# BeeBlue.net
KiCad netlist of a schematic drawn in EAGLE
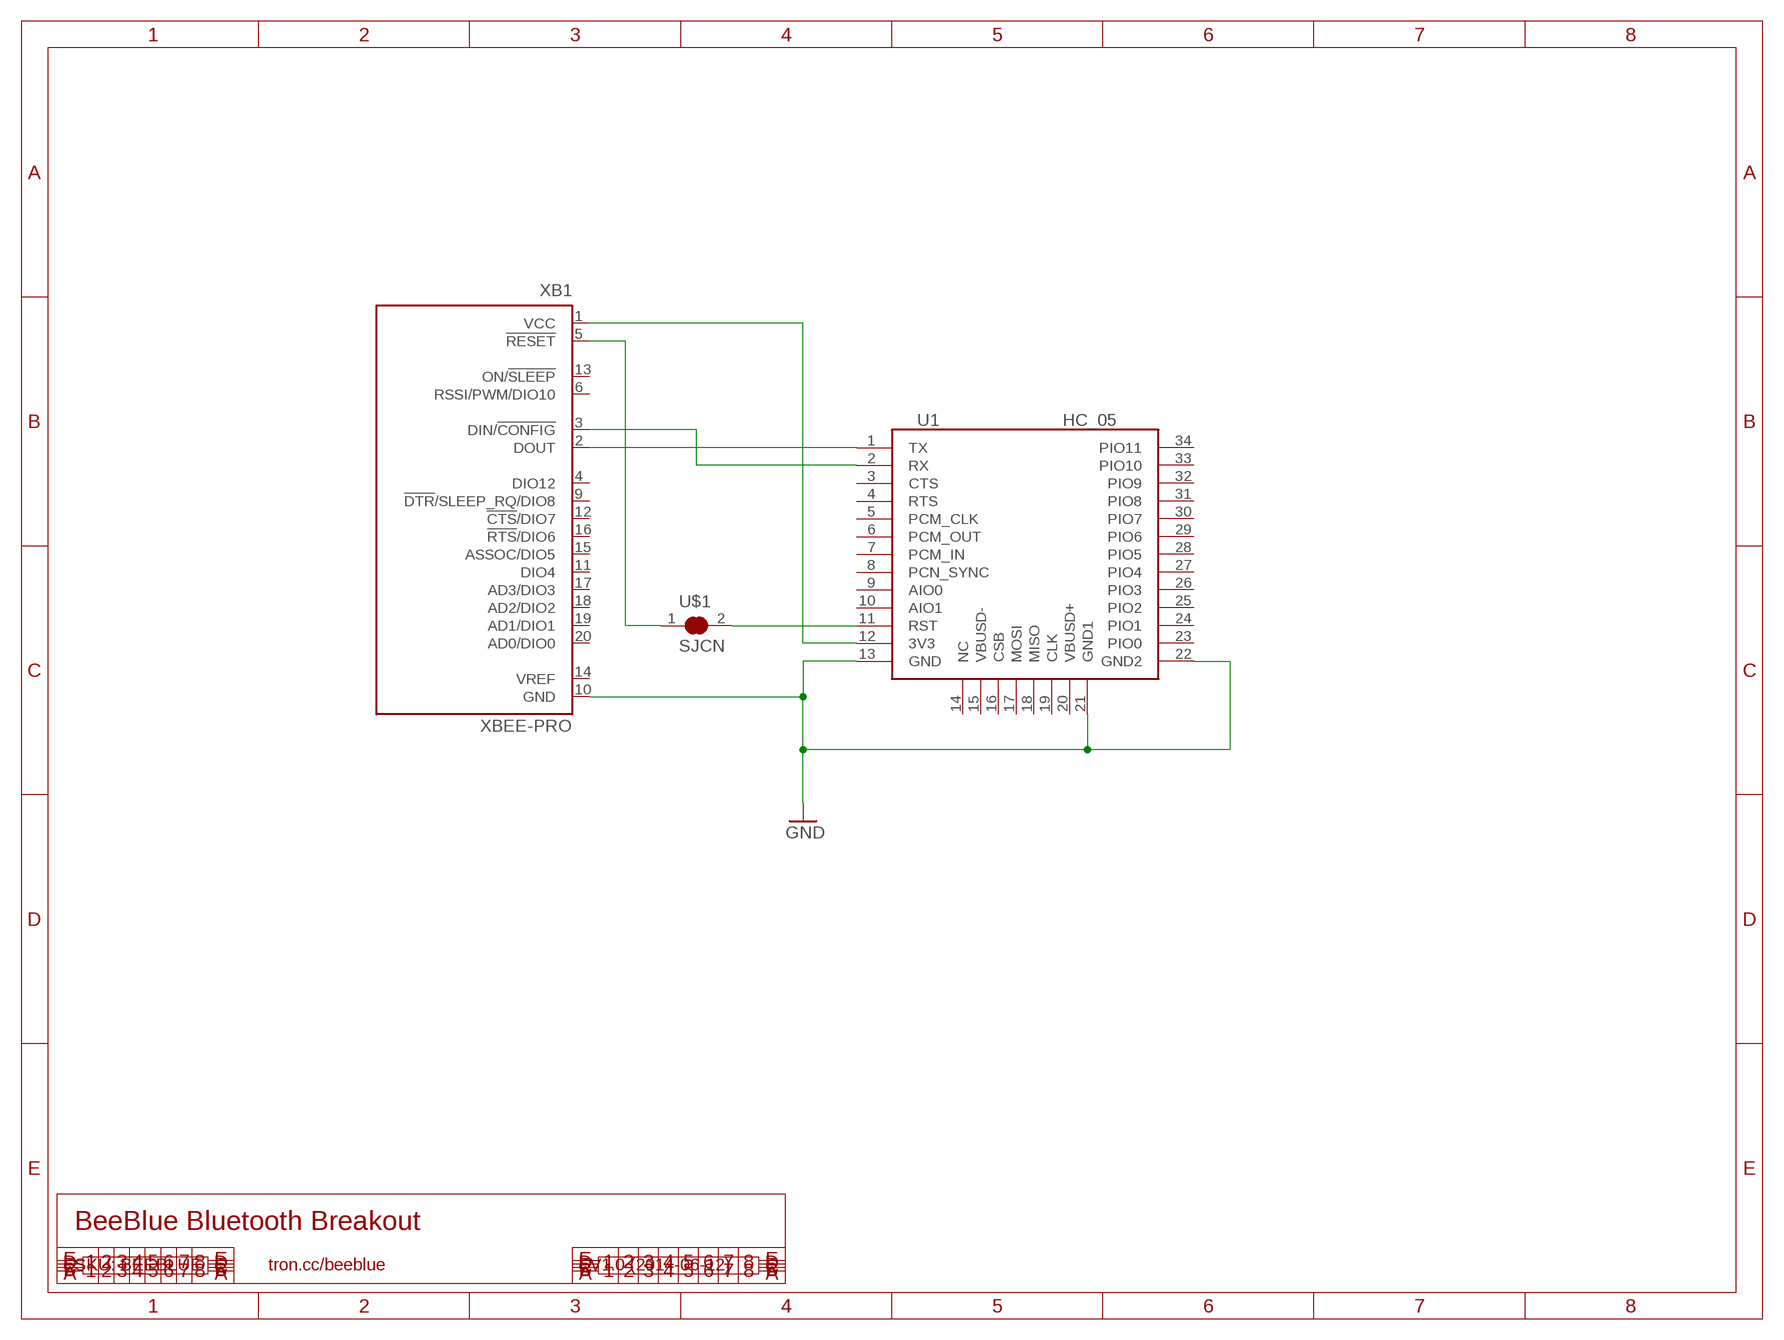
[diagram p0: schematic, sheet 1]

(export (version "E")
  (design (tool "Eeschema 10.0.6"))
  (components
    (comp (ref "U$1")
      (value "SJCN")
      (footprint "eagle-import:SJC")
      (libsource (lib "eagle-import") (part "SJCN"))
    )
    (comp (ref "U1")
      (value "HC_05")
      (footprint "eagle-import:BLUETOOTH_SMD")
      (libsource (lib "eagle-import") (part "HC_05"))
    )
    (comp (ref "XB1")
      (value "XBEE-PRO")
      (footprint "eagle-import:XBEE-PRO")
      (fields (field (name "MPN") "XBP24-AWI-001"))
      (libsource (lib "eagle-import") (part "XBEE-PRO"))
    )
  )
  (nets
    (net (code "1") (name "GND") (class "Default")
      (node (ref "U1") (pin "13") (pinfunction "GND_13") (pintype "bidirectional"))
      (node (ref "U1") (pin "21") (pinfunction "GND1_21") (pintype "bidirectional"))
      (node (ref "U1") (pin "22") (pinfunction "GND2_22") (pintype "bidirectional"))
      (node (ref "XB1") (pin "10") (pinfunction "GND_10") (pintype "power_in"))
    )
    (net (code "2") (name "Net-(U1-3V3)") (class "Default")
      (node (ref "U1") (pin "12") (pinfunction "3V3_12") (pintype "bidirectional"))
      (node (ref "XB1") (pin "1") (pinfunction "VCC_1") (pintype "power_in"))
    )
    (net (code "3") (name "Net-(U1-RST)") (class "Default")
      (node (ref "U$1") (pin "2") (pinfunction "2_2") (pintype "passive"))
      (node (ref "U1") (pin "11") (pinfunction "RST_11") (pintype "bidirectional"))
    )
    (net (code "4") (name "Net-(U1-RX)") (class "Default")
      (node (ref "U1") (pin "2") (pinfunction "RX_2") (pintype "bidirectional"))
      (node (ref "XB1") (pin "3") (pinfunction "DIN/~{CONFIG}_3") (pintype "input"))
    )
    (net (code "5") (name "Net-(U1-TX)") (class "Default")
      (node (ref "U1") (pin "1") (pinfunction "TX_1") (pintype "bidirectional"))
      (node (ref "XB1") (pin "2") (pinfunction "DOUT_2") (pintype "output"))
    )
    (net (code "6") (name "Net-(XB1-~{RESET})") (class "Default")
      (node (ref "U$1") (pin "1") (pinfunction "1_1") (pintype "passive"))
      (node (ref "XB1") (pin "5") (pinfunction "~{RESET}_5") (pintype "input"))
    )
    (net (code "7") (name "unconnected-(U1-AIO0-Pad9)") (class "Default")
      (node (ref "U1") (pin "9") (pinfunction "AIO0_9") (pintype "bidirectional"))
    )
    (net (code "8") (name "unconnected-(U1-AIO1-Pad10)") (class "Default")
      (node (ref "U1") (pin "10") (pinfunction "AIO1_10") (pintype "bidirectional"))
    )
    (net (code "9") (name "unconnected-(U1-CLK-Pad19)") (class "Default")
      (node (ref "U1") (pin "19") (pinfunction "CLK_19") (pintype "bidirectional"))
    )
    (net (code "10") (name "unconnected-(U1-CSB-Pad16)") (class "Default")
      (node (ref "U1") (pin "16") (pinfunction "CSB_16") (pintype "bidirectional"))
    )
    (net (code "11") (name "unconnected-(U1-CTS-Pad3)") (class "Default")
      (node (ref "U1") (pin "3") (pinfunction "CTS_3") (pintype "bidirectional"))
    )
    (net (code "12") (name "unconnected-(U1-MISO-Pad18)") (class "Default")
      (node (ref "U1") (pin "18") (pinfunction "MISO_18") (pintype "bidirectional"))
    )
    (net (code "13") (name "unconnected-(U1-MOSI-Pad17)") (class "Default")
      (node (ref "U1") (pin "17") (pinfunction "MOSI_17") (pintype "bidirectional"))
    )
    (net (code "14") (name "unconnected-(U1-NC-Pad14)") (class "Default")
      (node (ref "U1") (pin "14") (pinfunction "NC_14") (pintype "bidirectional"))
    )
    (net (code "15") (name "unconnected-(U1-PCM_CLK-Pad5)") (class "Default")
      (node (ref "U1") (pin "5") (pinfunction "PCM_CLK_5") (pintype "bidirectional"))
    )
    (net (code "16") (name "unconnected-(U1-PCM_IN-Pad7)") (class "Default")
      (node (ref "U1") (pin "7") (pinfunction "PCM_IN_7") (pintype "bidirectional"))
    )
    (net (code "17") (name "unconnected-(U1-PCM_OUT-Pad6)") (class "Default")
      (node (ref "U1") (pin "6") (pinfunction "PCM_OUT_6") (pintype "bidirectional"))
    )
    (net (code "18") (name "unconnected-(U1-PCN_SYNC-Pad8)") (class "Default")
      (node (ref "U1") (pin "8") (pinfunction "PCN_SYNC_8") (pintype "bidirectional"))
    )
    (net (code "19") (name "unconnected-(U1-PIO0-Pad23)") (class "Default")
      (node (ref "U1") (pin "23") (pinfunction "PIO0_23") (pintype "bidirectional"))
    )
    (net (code "20") (name "unconnected-(U1-PIO1-Pad24)") (class "Default")
      (node (ref "U1") (pin "24") (pinfunction "PIO1_24") (pintype "bidirectional"))
    )
    (net (code "21") (name "unconnected-(U1-PIO2-Pad25)") (class "Default")
      (node (ref "U1") (pin "25") (pinfunction "PIO2_25") (pintype "bidirectional"))
    )
    (net (code "22") (name "unconnected-(U1-PIO3-Pad26)") (class "Default")
      (node (ref "U1") (pin "26") (pinfunction "PIO3_26") (pintype "bidirectional"))
    )
    (net (code "23") (name "unconnected-(U1-PIO4-Pad27)") (class "Default")
      (node (ref "U1") (pin "27") (pinfunction "PIO4_27") (pintype "bidirectional"))
    )
    (net (code "24") (name "unconnected-(U1-PIO5-Pad28)") (class "Default")
      (node (ref "U1") (pin "28") (pinfunction "PIO5_28") (pintype "bidirectional"))
    )
    (net (code "25") (name "unconnected-(U1-PIO6-Pad29)") (class "Default")
      (node (ref "U1") (pin "29") (pinfunction "PIO6_29") (pintype "bidirectional"))
    )
    (net (code "26") (name "unconnected-(U1-PIO7-Pad30)") (class "Default")
      (node (ref "U1") (pin "30") (pinfunction "PIO7_30") (pintype "bidirectional"))
    )
    (net (code "27") (name "unconnected-(U1-PIO8-Pad31)") (class "Default")
      (node (ref "U1") (pin "31") (pinfunction "PIO8_31") (pintype "bidirectional"))
    )
    (net (code "28") (name "unconnected-(U1-PIO9-Pad32)") (class "Default")
      (node (ref "U1") (pin "32") (pinfunction "PIO9_32") (pintype "bidirectional"))
    )
    (net (code "29") (name "unconnected-(U1-PIO10-Pad33)") (class "Default")
      (node (ref "U1") (pin "33") (pinfunction "PIO10_33") (pintype "bidirectional"))
    )
    (net (code "30") (name "unconnected-(U1-PIO11-Pad34)") (class "Default")
      (node (ref "U1") (pin "34") (pinfunction "PIO11_34") (pintype "bidirectional"))
    )
    (net (code "31") (name "unconnected-(U1-RTS-Pad4)") (class "Default")
      (node (ref "U1") (pin "4") (pinfunction "RTS_4") (pintype "bidirectional"))
    )
    (net (code "32") (name "unconnected-(U1-VBUSD+-Pad20)") (class "Default")
      (node (ref "U1") (pin "20") (pinfunction "VBUSD+_20") (pintype "bidirectional"))
    )
    (net (code "33") (name "unconnected-(U1-VBUSD--Pad15)") (class "Default")
      (node (ref "U1") (pin "15") (pinfunction "VBUSD-_15") (pintype "bidirectional"))
    )
    (net (code "34") (name "unconnected-(XB1-AD0{slash}DIO0-Pad20)") (class "Default")
      (node (ref "XB1") (pin "20") (pinfunction "AD0/DIO0_20") (pintype "bidirectional"))
    )
    (net (code "35") (name "unconnected-(XB1-AD1{slash}DIO1-Pad19)") (class "Default")
      (node (ref "XB1") (pin "19") (pinfunction "AD1/DIO1_19") (pintype "bidirectional"))
    )
    (net (code "36") (name "unconnected-(XB1-AD2{slash}DIO2-Pad18)") (class "Default")
      (node (ref "XB1") (pin "18") (pinfunction "AD2/DIO2_18") (pintype "bidirectional"))
    )
    (net (code "37") (name "unconnected-(XB1-AD3{slash}DIO3-Pad17)") (class "Default")
      (node (ref "XB1") (pin "17") (pinfunction "AD3/DIO3_17") (pintype "bidirectional"))
    )
    (net (code "38") (name "unconnected-(XB1-ASSOC{slash}DIO5-Pad15)") (class "Default")
      (node (ref "XB1") (pin "15") (pinfunction "ASSOC/DIO5_15") (pintype "bidirectional"))
    )
    (net (code "39") (name "unconnected-(XB1-DIO4-Pad11)") (class "Default")
      (node (ref "XB1") (pin "11") (pinfunction "DIO4_11") (pintype "bidirectional"))
    )
    (net (code "40") (name "unconnected-(XB1-DIO12-Pad4)") (class "Default")
      (node (ref "XB1") (pin "4") (pinfunction "DIO12_4") (pintype "bidirectional"))
    )
    (net (code "41") (name "unconnected-(XB1-ON{slash}~{SLEEP}-Pad13)") (class "Default")
      (node (ref "XB1") (pin "13") (pinfunction "ON/~{SLEEP}_13") (pintype "output"))
    )
    (net (code "42") (name "unconnected-(XB1-RSSI{slash}PWM{slash}DIO10-Pad6)") (class "Default")
      (node (ref "XB1") (pin "6") (pinfunction "RSSI/PWM/DIO10_6") (pintype "output"))
    )
    (net (code "43") (name "unconnected-(XB1-VREF-Pad14)") (class "Default")
      (node (ref "XB1") (pin "14") (pinfunction "VREF_14") (pintype "input"))
    )
    (net (code "44") (name "unconnected-(XB1-~{CTS}{slash}DIO7-Pad12)") (class "Default")
      (node (ref "XB1") (pin "12") (pinfunction "~{CTS}/DIO7_12") (pintype "bidirectional"))
    )
    (net (code "45") (name "unconnected-(XB1-~{DTR}{slash}SLEEP_RQ{slash}DIO8-Pad9)") (class "Default")
      (node (ref "XB1") (pin "9") (pinfunction "~{DTR}/SLEEP_RQ/DIO8_9") (pintype "bidirectional"))
    )
    (net (code "46") (name "unconnected-(XB1-~{RTS}{slash}DIO6-Pad16)") (class "Default")
      (node (ref "XB1") (pin "16") (pinfunction "~{RTS}/DIO6_16") (pintype "bidirectional"))
    )
  )
)
